# wssf_arduino_nano_server.net
KiCad netlist of a schematic drawn in EAGLE
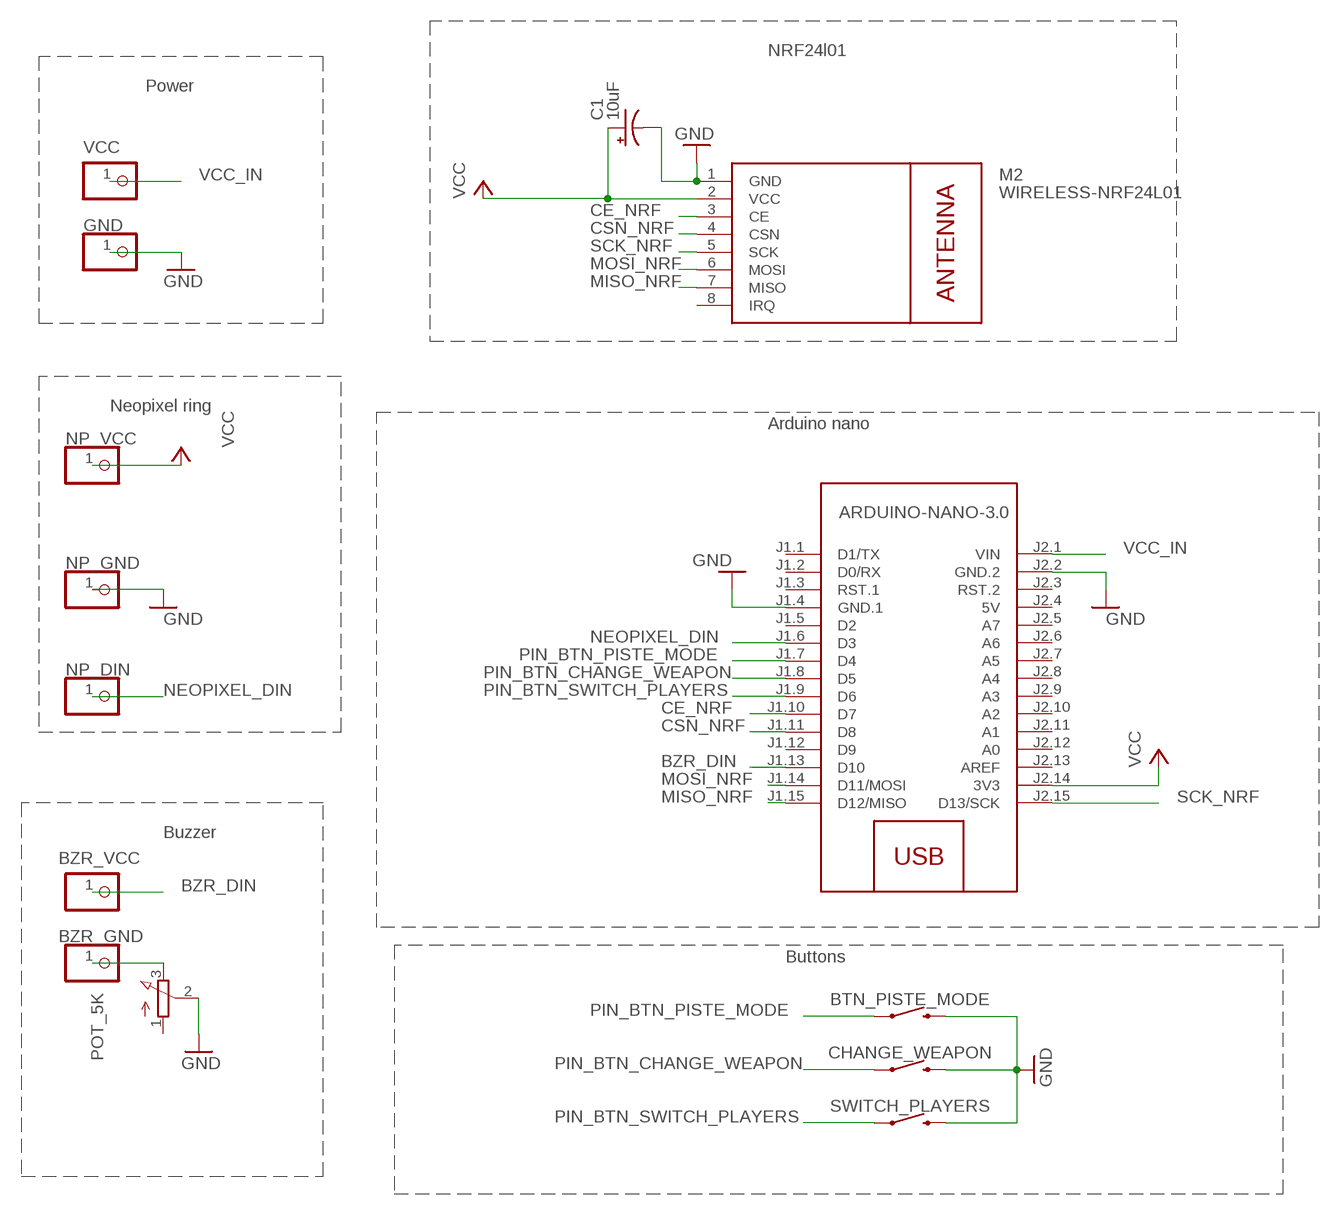
[diagram p0: schematic, sheet 1]

(export (version "E")
  (design (tool "Eeschema 10.0.6"))
  (components
    (comp (ref "BTN_PISTE_MODE")
      (value "MOMENTARY-SWITCH-SPST-PTH-RIGHT-ANGLE-KIT")
      (footprint "eagle-import:TACTILE_SWITCH_PTH_RIGHT_ANGLE_KIT")
      (libsource (lib "eagle-import") (part "MOMENTARY-SWITCH-SPST-PTH-RIGHT-ANGLE-KIT"))
    )
    (comp (ref "BZR_GND")
      (value "BZR_GND")
      (footprint "eagle-import:1X01")
      (libsource (lib "eagle-import") (part "PINHD-1X1"))
    )
    (comp (ref "BZR_VCC")
      (value "BZR_VCC")
      (footprint "eagle-import:1X01")
      (libsource (lib "eagle-import") (part "PINHD-1X1"))
    )
    (comp (ref "C1")
      (value "10uF")
      (footprint "eagle-import:E2-5")
      (libsource (lib "eagle-import") (part "CPOL-USE2-5"))
    )
    (comp (ref "CHANGE_WEAPON")
      (value "MOMENTARY-SWITCH-SPST-PTH-RIGHT-ANGLE-KIT")
      (footprint "eagle-import:TACTILE_SWITCH_PTH_RIGHT_ANGLE_KIT")
      (libsource (lib "eagle-import") (part "MOMENTARY-SWITCH-SPST-PTH-RIGHT-ANGLE-KIT"))
    )
    (comp (ref "GND")
      (value "GND")
      (footprint "eagle-import:1X01")
      (libsource (lib "eagle-import") (part "PINHD-1X1"))
    )
    (comp (ref "M1")
      (value "ARDUINO-NANO-3.0")
      (footprint "eagle-import:ARDUINO-NANO-3.0")
      (libsource (lib "eagle-import") (part "ARDUINO-NANO-3.0"))
    )
    (comp (ref "M2")
      (value "WIRELESS-NRF24L01")
      (footprint "eagle-import:WIRELESS-NRF24L01")
      (libsource (lib "eagle-import") (part "WIRELESS-NRF24L01"))
    )
    (comp (ref "NP_DIN")
      (value "NP_DIN")
      (footprint "eagle-import:1X01")
      (libsource (lib "eagle-import") (part "PINHD-1X1"))
    )
    (comp (ref "NP_GND")
      (value "NP_GND")
      (footprint "eagle-import:1X01")
      (libsource (lib "eagle-import") (part "PINHD-1X1"))
    )
    (comp (ref "NP_VCC")
      (value "NP_VCC")
      (footprint "eagle-import:1X01")
      (libsource (lib "eagle-import") (part "PINHD-1X1"))
    )
    (comp (ref "POT_5K")
      (value "3RP/1610N")
      (footprint "eagle-import:3RP_1610N")
      (libsource (lib "eagle-import") (part "3RP/1610N"))
    )
    (comp (ref "SWITCH_PLAYERS")
      (value "MOMENTARY-SWITCH-SPST-PTH-RIGHT-ANGLE-KIT")
      (footprint "eagle-import:TACTILE_SWITCH_PTH_RIGHT_ANGLE_KIT")
      (libsource (lib "eagle-import") (part "MOMENTARY-SWITCH-SPST-PTH-RIGHT-ANGLE-KIT"))
    )
    (comp (ref "VCC")
      (value "VCC")
      (footprint "eagle-import:1X01")
      (libsource (lib "eagle-import") (part "PINHD-1X1"))
    )
  )
  (nets
    (net (code "1") (name "/5V") (class "Default")
      (node (ref "M1") (pin "J2.4") (pinfunction "5V_J2.4") (pintype "power_in"))
    )
    (net (code "2") (name "/BZR_DIN") (class "Default")
      (node (ref "BZR_VCC") (pin "1") (pinfunction "1_1") (pintype "passive"))
      (node (ref "M1") (pin "J1.13") (pinfunction "D10_J1.13") (pintype "bidirectional"))
    )
    (net (code "3") (name "/CE_NRF") (class "Default")
      (node (ref "M1") (pin "J1.10") (pinfunction "D7_J1.10") (pintype "bidirectional"))
      (node (ref "M2") (pin "3") (pinfunction "CE_3") (pintype "bidirectional"))
    )
    (net (code "4") (name "/CSN_NRF") (class "Default")
      (node (ref "M1") (pin "J1.11") (pinfunction "D8_J1.11") (pintype "bidirectional"))
      (node (ref "M2") (pin "4") (pinfunction "CSN_4") (pintype "bidirectional"))
    )
    (net (code "5") (name "/MISO_NRF") (class "Default")
      (node (ref "M1") (pin "J1.15") (pinfunction "D12/MISO_J1.15") (pintype "bidirectional"))
      (node (ref "M2") (pin "7") (pinfunction "MISO_7") (pintype "bidirectional"))
    )
    (net (code "6") (name "/MOSI_NRF") (class "Default")
      (node (ref "M1") (pin "J1.14") (pinfunction "D11/MOSI_J1.14") (pintype "bidirectional"))
      (node (ref "M2") (pin "6") (pinfunction "MOSI_6") (pintype "bidirectional"))
    )
    (net (code "7") (name "/NEOPIXEL_DIN") (class "Default")
      (node (ref "M1") (pin "J1.6") (pinfunction "D3_J1.6") (pintype "bidirectional"))
      (node (ref "NP_DIN") (pin "1") (pinfunction "1_1") (pintype "passive"))
    )
    (net (code "8") (name "/PIN_BTN_CHANGE_WEAPON") (class "Default")
      (node (ref "CHANGE_WEAPON") (pin "1") (pinfunction "1_1") (pintype "passive"))
      (node (ref "M1") (pin "J1.8") (pinfunction "D5_J1.8") (pintype "bidirectional"))
    )
    (net (code "9") (name "/PIN_BTN_PISTE_MODE") (class "Default")
      (node (ref "BTN_PISTE_MODE") (pin "1") (pinfunction "1_1") (pintype "passive"))
      (node (ref "M1") (pin "J1.7") (pinfunction "D4_J1.7") (pintype "bidirectional"))
    )
    (net (code "10") (name "/PIN_BTN_SWITCH_PLAYERS") (class "Default")
      (node (ref "M1") (pin "J1.9") (pinfunction "D6_J1.9") (pintype "bidirectional"))
      (node (ref "SWITCH_PLAYERS") (pin "1") (pinfunction "1_1") (pintype "passive"))
    )
    (net (code "11") (name "/SCK_NRF") (class "Default")
      (node (ref "M1") (pin "J2.15") (pinfunction "D13/SCK_J2.15") (pintype "bidirectional"))
      (node (ref "M2") (pin "5") (pinfunction "SCK_5") (pintype "bidirectional"))
    )
    (net (code "12") (name "/VCC_IN") (class "Default")
      (node (ref "M1") (pin "J2.1") (pinfunction "VIN_J2.1") (pintype "power_in"))
      (node (ref "VCC") (pin "1") (pinfunction "1_1") (pintype "passive"))
    )
    (net (code "13") (name "GND") (class "Default")
      (node (ref "BTN_PISTE_MODE") (pin "2") (pinfunction "2_2") (pintype "passive"))
      (node (ref "C1") (pin "-") (pinfunction "-_-") (pintype "passive"))
      (node (ref "CHANGE_WEAPON") (pin "2") (pinfunction "2_2") (pintype "passive"))
      (node (ref "GND") (pin "1") (pinfunction "1_1") (pintype "passive"))
      (node (ref "M1") (pin "J1.4") (pinfunction "GND.1_J1.4") (pintype "power_in"))
      (node (ref "M1") (pin "J2.2") (pinfunction "GND.2_J2.2") (pintype "power_in"))
      (node (ref "M2") (pin "1") (pinfunction "GND_1") (pintype "power_in"))
      (node (ref "NP_GND") (pin "1") (pinfunction "1_1") (pintype "passive"))
      (node (ref "POT_5K") (pin "2") (pinfunction "S_2") (pintype "passive"))
      (node (ref "SWITCH_PLAYERS") (pin "2") (pinfunction "2_2") (pintype "passive"))
    )
    (net (code "14") (name "Net-(POT_5K-E)") (class "Default")
      (node (ref "BZR_GND") (pin "1") (pinfunction "1_1") (pintype "passive"))
      (node (ref "POT_5K") (pin "3") (pinfunction "E_3") (pintype "passive"))
    )
    (net (code "15") (name "VCC") (class "Default")
      (node (ref "C1") (pin "+") (pinfunction "+_+") (pintype "passive"))
      (node (ref "M1") (pin "J2.14") (pinfunction "3V3_J2.14") (pintype "power_in"))
      (node (ref "M2") (pin "2") (pinfunction "VCC_2") (pintype "power_in"))
      (node (ref "NP_VCC") (pin "1") (pinfunction "1_1") (pintype "passive"))
    )
    (net (code "16") (name "unconnected-(M1-A0-PadJ2.12)") (class "Default")
      (node (ref "M1") (pin "J2.12") (pinfunction "A0_J2.12") (pintype "bidirectional"))
    )
    (net (code "17") (name "unconnected-(M1-A1-PadJ2.11)") (class "Default")
      (node (ref "M1") (pin "J2.11") (pinfunction "A1_J2.11") (pintype "bidirectional"))
    )
    (net (code "18") (name "unconnected-(M1-A2-PadJ2.10)") (class "Default")
      (node (ref "M1") (pin "J2.10") (pinfunction "A2_J2.10") (pintype "bidirectional"))
    )
    (net (code "19") (name "unconnected-(M1-A3-PadJ2.9)") (class "Default")
      (node (ref "M1") (pin "J2.9") (pinfunction "A3_J2.9") (pintype "bidirectional"))
    )
    (net (code "20") (name "unconnected-(M1-A4-PadJ2.8)") (class "Default")
      (node (ref "M1") (pin "J2.8") (pinfunction "A4_J2.8") (pintype "bidirectional"))
    )
    (net (code "21") (name "unconnected-(M1-A5-PadJ2.7)") (class "Default")
      (node (ref "M1") (pin "J2.7") (pinfunction "A5_J2.7") (pintype "bidirectional"))
    )
    (net (code "22") (name "unconnected-(M1-A6-PadJ2.6)") (class "Default")
      (node (ref "M1") (pin "J2.6") (pinfunction "A6_J2.6") (pintype "bidirectional"))
    )
    (net (code "23") (name "unconnected-(M1-A7-PadJ2.5)") (class "Default")
      (node (ref "M1") (pin "J2.5") (pinfunction "A7_J2.5") (pintype "bidirectional"))
    )
    (net (code "24") (name "unconnected-(M1-AREF-PadJ2.13)") (class "Default")
      (node (ref "M1") (pin "J2.13") (pinfunction "AREF_J2.13") (pintype "bidirectional"))
    )
    (net (code "25") (name "unconnected-(M1-D0{slash}RX-PadJ1.2)") (class "Default")
      (node (ref "M1") (pin "J1.2") (pinfunction "D0/RX_J1.2") (pintype "bidirectional"))
    )
    (net (code "26") (name "unconnected-(M1-D1{slash}TX-PadJ1.1)") (class "Default")
      (node (ref "M1") (pin "J1.1") (pinfunction "D1/TX_J1.1") (pintype "bidirectional"))
    )
    (net (code "27") (name "unconnected-(M1-D2-PadJ1.5)") (class "Default")
      (node (ref "M1") (pin "J1.5") (pinfunction "D2_J1.5") (pintype "bidirectional"))
    )
    (net (code "28") (name "unconnected-(M1-D9-PadJ1.12)") (class "Default")
      (node (ref "M1") (pin "J1.12") (pinfunction "D9_J1.12") (pintype "bidirectional"))
    )
    (net (code "29") (name "unconnected-(M1-RST.1-PadJ1.3)") (class "Default")
      (node (ref "M1") (pin "J1.3") (pinfunction "RST.1_J1.3") (pintype "bidirectional"))
    )
    (net (code "30") (name "unconnected-(M1-RST.2-PadJ2.3)") (class "Default")
      (node (ref "M1") (pin "J2.3") (pinfunction "RST.2_J2.3") (pintype "bidirectional"))
    )
    (net (code "31") (name "unconnected-(M2-IRQ-Pad8)") (class "Default")
      (node (ref "M2") (pin "8") (pinfunction "IRQ_8") (pintype "bidirectional"))
    )
    (net (code "32") (name "unconnected-(POT_5K-A-Pad1)") (class "Default")
      (node (ref "POT_5K") (pin "1") (pinfunction "A_1") (pintype "passive"))
    )
  )
)
